# BV100011_ControlTopLevel.net
KiCad netlist of a schematic drawn in Altium Designer
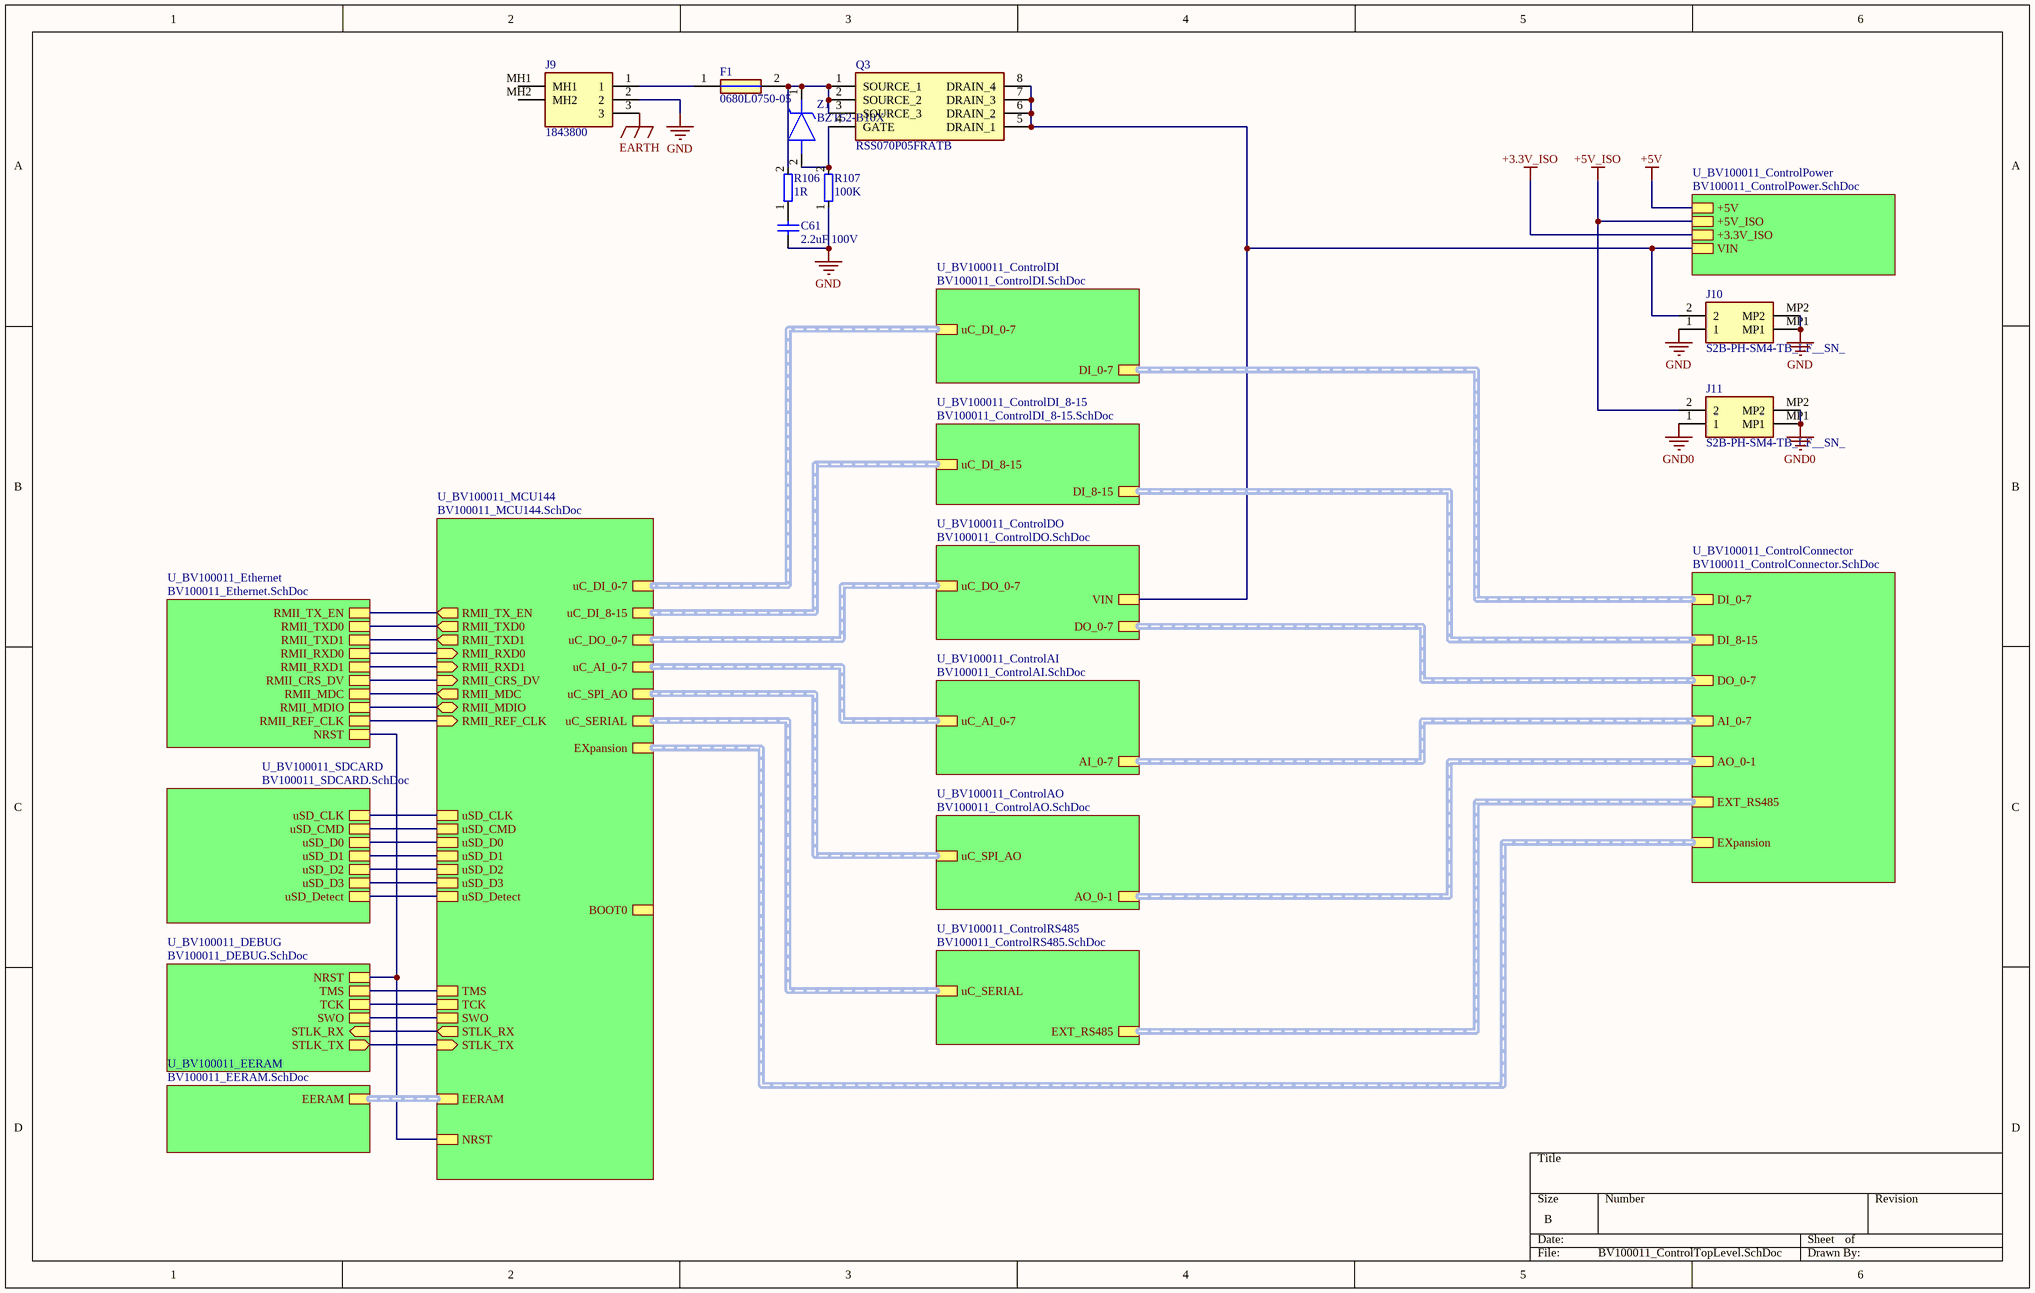
[diagram p0: BV100011_ControlTopLevel.SchDoc]

(export (version "E")
  (design (tool "Eeschema 10.0.6"))
  (components
    (comp (ref "C61")
      (value "2.2uF 100V")
      (footprint "C1210")
      (description "Capacitor")
      (fields (field (name "PUBLISHER") "Altium Limited"))
      (libsource (lib "Miscellaneous Devices") (part "Cap"))
    )
    (comp (ref "F1")
      (value "0680L0750-05")
      (footprint "SamacSys:FUSC6125X279N")
      (description "Fuse")
      (fields (field (name "MOUSER PART NUMBER") "530-0680L0750-05"))
      (libsource (lib "*") (part "0680L0750-05"))
    )
    (comp (ref "J9")
      (value "1843800")
      (footprint "SamacSys:1843800")
      (description "Connector")
      (fields (field (name "MOUSER PART NUMBER") "651-1843800"))
      (libsource (lib "*") (part "1843800"))
    )
    (comp (ref "J10")
      (value "S2B-PH-SM4-TB_LF__SN_")
      (footprint "SamacSys:S2BPHSM4TBLFSN")
      (description "Connector")
      (fields (field (name "MANUFACTURER_PART_NUMBER") "S2B-PH-SM4-TB(LF)(SN)"))
      (libsource (lib "*") (part "S2B-PH-SM4-TB_LF__SN_"))
    )
    (comp (ref "J11")
      (value "S2B-PH-SM4-TB_LF__SN_")
      (footprint "SamacSys:S2BPHSM4TBLFSN")
      (description "Connector")
      (fields (field (name "MANUFACTURER_PART_NUMBER") "S2B-PH-SM4-TB(LF)(SN)"))
      (libsource (lib "*") (part "S2B-PH-SM4-TB_LF__SN_"))
    )
    (comp (ref "Q3")
      (value "RSS070P05FRATB")
      (footprint "SamacSys:SOIC127P600X175-8N")
      (description "MOSFET (P-Channel)")
      (fields (field (name "MOUSER PART NUMBER") "755-RSS070P05FRATB"))
      (libsource (lib "*") (part "RSS070P05FRATB"))
    )
    (comp (ref "R106")
      (value "1R")
      (footprint "R0805")
      (description "Resistor")
      (libsource (lib "要多酷有多库") (part "电阻（1）"))
    )
    (comp (ref "R107")
      (value "100K")
      (footprint "R0603")
      (description "Resistor")
      (libsource (lib "要多酷有多库") (part "电阻（1）"))
    )
    (comp (ref "Z1")
      (value "BZT52-B10X")
      (footprint "SamacSys:SODFL3616X130N")
      (description "Zener Diode")
      (fields (field (name "MOUSER PART NUMBER") "771-BZT52-B10X"))
      (libsource (lib "*") (part "BZT52-B10X"))
    )
  )
  (nets
    (net (code "3") (name "+5V_ISO") (class "Default")
      (node (ref "J11") (pin "2") (pinfunction "2_2") (pintype "passive"))
    )
    (net (code "28") (name "/VIN") (class "Default")
      (node (ref "J10") (pin "2") (pinfunction "2_2") (pintype "passive"))
      (node (ref "Q3") (pin "5") (pinfunction "DRAIN_1_5") (pintype "passive"))
      (node (ref "Q3") (pin "6") (pinfunction "DRAIN_2_6") (pintype "passive"))
      (node (ref "Q3") (pin "7") (pinfunction "DRAIN_3_7") (pintype "passive"))
      (node (ref "Q3") (pin "8") (pinfunction "DRAIN_4_8") (pintype "passive"))
    )
    (net (code "42") (name "EARTH") (class "Default")
      (node (ref "J9") (pin "3") (pinfunction "3_3") (pintype "passive"))
    )
    (net (code "43") (name "GND") (class "Default")
      (node (ref "C61") (pin "1") (pinfunction "1_1") (pintype "passive"))
      (node (ref "J10") (pin "1") (pinfunction "1_1") (pintype "passive"))
      (node (ref "J10") (pin "MP1") (pinfunction "MP1_MP1") (pintype "passive"))
      (node (ref "J10") (pin "MP2") (pinfunction "MP2_MP2") (pintype "passive"))
      (node (ref "J9") (pin "2") (pinfunction "2_2") (pintype "passive"))
      (node (ref "R107") (pin "1") (pinfunction "1_1") (pintype "passive"))
    )
    (net (code "44") (name "GND0") (class "Default")
      (node (ref "J11") (pin "1") (pinfunction "1_1") (pintype "passive"))
      (node (ref "J11") (pin "MP1") (pinfunction "MP1_MP1") (pintype "passive"))
      (node (ref "J11") (pin "MP2") (pinfunction "MP2_MP2") (pintype "passive"))
    )
    (net (code "45") (name "Net-(C61-Pad2)") (class "Default")
      (node (ref "C61") (pin "2") (pinfunction "2_2") (pintype "passive"))
      (node (ref "R106") (pin "1") (pinfunction "1_1") (pintype "passive"))
    )
    (net (code "46") (name "Net-(F1-Pad1)") (class "Default")
      (node (ref "F1") (pin "1") (pinfunction "1_1") (pintype "passive"))
      (node (ref "J9") (pin "1") (pinfunction "1_1") (pintype "passive"))
    )
    (net (code "47") (name "Net-(Q3-GATE)") (class "Default")
      (node (ref "Q3") (pin "4") (pinfunction "GATE_4") (pintype "passive"))
      (node (ref "R107") (pin "2") (pinfunction "2_2") (pintype "passive"))
      (node (ref "Z1") (pin "2") (pinfunction "A_2") (pintype "passive"))
    )
    (net (code "48") (name "Net-(Q3-SOURCE_1)") (class "Default")
      (node (ref "F1") (pin "2") (pinfunction "2_2") (pintype "passive"))
      (node (ref "Q3") (pin "1") (pinfunction "SOURCE_1_1") (pintype "passive"))
      (node (ref "Q3") (pin "2") (pinfunction "SOURCE_2_2") (pintype "passive"))
      (node (ref "Q3") (pin "3") (pinfunction "SOURCE_3_3") (pintype "passive"))
      (node (ref "R106") (pin "2") (pinfunction "2_2") (pintype "passive"))
      (node (ref "Z1") (pin "1") (pinfunction "K_1") (pintype "passive"))
    )
    (net (code "49") (name "unconnected-(J9-PadMH1)") (class "Default")
      (node (ref "J9") (pin "MH1") (pinfunction "MH1_MH1") (pintype "passive"))
    )
    (net (code "50") (name "unconnected-(J9-PadMH2)") (class "Default")
      (node (ref "J9") (pin "MH2") (pinfunction "MH2_MH2") (pintype "passive"))
    )
  )
)
